# CubeControl.net
KiCad netlist of a schematic drawn in Altium Designer
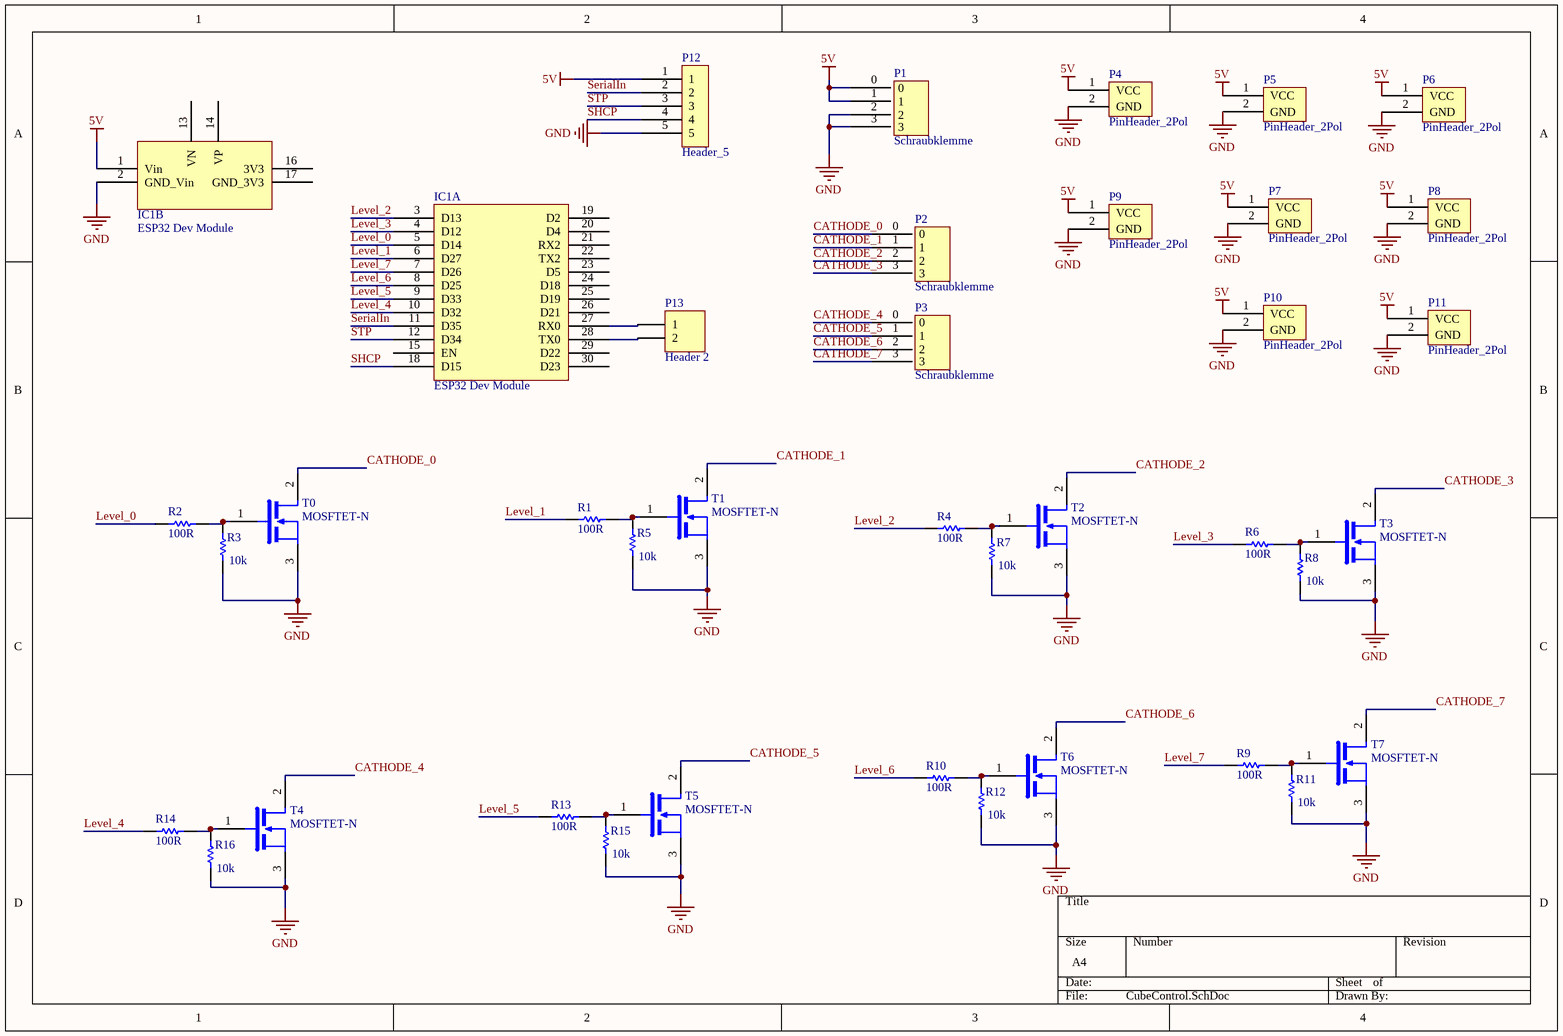
[diagram p0: CubeControl.SchDoc]

(export (version "E")
  (design (tool "Eeschema 10.0.6"))
  (components
    (comp (ref "IC1")
      (value "ESP32 Dev Module")
      (footprint "ESP32 Dev Module")
      (libsource (lib "RGB-Cube") (part "ESP32 Dev Module"))
    )
    (comp (ref "P1")
      (value "Schraubklemme")
      (footprint "Schraubklemme 4Pol")
      (description "Reichelt: RND 205-00003")
      (libsource (lib "RGB-Cube") (part "Schraubklemme"))
    )
    (comp (ref "P2")
      (value "Schraubklemme")
      (footprint "Schraubklemme 4Pol")
      (description "Reichelt: RND 205-00003")
      (libsource (lib "RGB-Cube") (part "Schraubklemme"))
    )
    (comp (ref "P3")
      (value "Schraubklemme")
      (footprint "Schraubklemme 4Pol")
      (description "Reichelt: RND 205-00003")
      (libsource (lib "RGB-Cube") (part "Schraubklemme"))
    )
    (comp (ref "P4")
      (value "PinHeader_2Pol")
      (footprint "PinHeader_2Pol")
      (libsource (lib "RGB-Cube") (part "PinHeader_2Pol"))
    )
    (comp (ref "P5")
      (value "PinHeader_2Pol")
      (footprint "PinHeader_2Pol")
      (libsource (lib "RGB-Cube") (part "PinHeader_2Pol"))
    )
    (comp (ref "P6")
      (value "PinHeader_2Pol")
      (footprint "PinHeader_2Pol")
      (libsource (lib "RGB-Cube") (part "PinHeader_2Pol"))
    )
    (comp (ref "P7")
      (value "PinHeader_2Pol")
      (footprint "PinHeader_2Pol")
      (libsource (lib "RGB-Cube") (part "PinHeader_2Pol"))
    )
    (comp (ref "P8")
      (value "PinHeader_2Pol")
      (footprint "PinHeader_2Pol")
      (libsource (lib "RGB-Cube") (part "PinHeader_2Pol"))
    )
    (comp (ref "P9")
      (value "PinHeader_2Pol")
      (footprint "PinHeader_2Pol")
      (libsource (lib "RGB-Cube") (part "PinHeader_2Pol"))
    )
    (comp (ref "P10")
      (value "PinHeader_2Pol")
      (footprint "PinHeader_2Pol")
      (libsource (lib "RGB-Cube") (part "PinHeader_2Pol"))
    )
    (comp (ref "P11")
      (value "PinHeader_2Pol")
      (footprint "PinHeader_2Pol")
      (libsource (lib "RGB-Cube") (part "PinHeader_2Pol"))
    )
    (comp (ref "P12")
      (value "Header_5")
      (footprint "PinHeader")
      (libsource (lib "RGB-Cube") (part "Header_5"))
    )
    (comp (ref "P13")
      (value "Header 2")
      (footprint "HDR1X2")
      (description "Header, 2-Pin")
      (fields (field (name "PUBLISHER") "Altium Limited"))
      (libsource (lib "Miscellaneous Connectors") (part "Header 2"))
    )
    (comp (ref "R1")
      (value "100R")
      (footprint "RESC1206(3216)_M")
      (description "2R 0.25W 5% 1206 (3216 Metric)  SMD")
      (fields (field (name "TOLERANCE") "5 %") (field (name "POWER") "0.25 W"))
      (libsource (lib "Altium Content Vault") (part "CMP-1014-00009-1"))
    )
    (comp (ref "R2")
      (value "100R")
      (footprint "RESC1206(3216)_M")
      (description "2R 0.25W 5% 1206 (3216 Metric)  SMD")
      (fields (field (name "TOLERANCE") "5 %") (field (name "POWER") "0.25 W"))
      (libsource (lib "Altium Content Vault") (part "CMP-1014-00009-1"))
    )
    (comp (ref "R3")
      (value "10k")
      (footprint "RESC1206(3216)_M")
      (description "43k 0.25W 5% 1206 (3216 Metric)  SMD")
      (fields (field (name "TOLERANCE") "5 %") (field (name "POWER") "0.25 W"))
      (libsource (lib "Altium Content Vault") (part "CMP-1014-00009-1"))
    )
    (comp (ref "R4")
      (value "100R")
      (footprint "RESC1206(3216)_M")
      (description "2R 0.25W 5% 1206 (3216 Metric)  SMD")
      (fields (field (name "TOLERANCE") "5 %") (field (name "POWER") "0.25 W"))
      (libsource (lib "Altium Content Vault") (part "CMP-1014-00009-1"))
    )
    (comp (ref "R5")
      (value "10k")
      (footprint "RESC1206(3216)_M")
      (description "43k 0.25W 5% 1206 (3216 Metric)  SMD")
      (fields (field (name "TOLERANCE") "5 %") (field (name "POWER") "0.25 W"))
      (libsource (lib "Altium Content Vault") (part "CMP-1014-00009-1"))
    )
    (comp (ref "R6")
      (value "100R")
      (footprint "RESC1206(3216)_M")
      (description "2R 0.25W 5% 1206 (3216 Metric)  SMD")
      (fields (field (name "TOLERANCE") "5 %") (field (name "POWER") "0.25 W"))
      (libsource (lib "Altium Content Vault") (part "CMP-1014-00009-1"))
    )
    (comp (ref "R7")
      (value "10k")
      (footprint "RESC1206(3216)_M")
      (description "43k 0.25W 5% 1206 (3216 Metric)  SMD")
      (fields (field (name "TOLERANCE") "5 %") (field (name "POWER") "0.25 W"))
      (libsource (lib "Altium Content Vault") (part "CMP-1014-00009-1"))
    )
    (comp (ref "R8")
      (value "10k")
      (footprint "RESC1206(3216)_M")
      (description "43k 0.25W 5% 1206 (3216 Metric)  SMD")
      (fields (field (name "TOLERANCE") "5 %") (field (name "POWER") "0.25 W"))
      (libsource (lib "Altium Content Vault") (part "CMP-1014-00009-1"))
    )
    (comp (ref "R9")
      (value "100R")
      (footprint "RESC1206(3216)_M")
      (description "2R 0.25W 5% 1206 (3216 Metric)  SMD")
      (fields (field (name "TOLERANCE") "5 %") (field (name "POWER") "0.25 W"))
      (libsource (lib "Altium Content Vault") (part "CMP-1014-00009-1"))
    )
    (comp (ref "R10")
      (value "100R")
      (footprint "RESC1206(3216)_M")
      (description "2R 0.25W 5% 1206 (3216 Metric)  SMD")
      (fields (field (name "TOLERANCE") "5 %") (field (name "POWER") "0.25 W"))
      (libsource (lib "Altium Content Vault") (part "CMP-1014-00009-1"))
    )
    (comp (ref "R11")
      (value "10k")
      (footprint "RESC1206(3216)_M")
      (description "43k 0.25W 5% 1206 (3216 Metric)  SMD")
      (fields (field (name "TOLERANCE") "5 %") (field (name "POWER") "0.25 W"))
      (libsource (lib "Altium Content Vault") (part "CMP-1014-00009-1"))
    )
    (comp (ref "R12")
      (value "10k")
      (footprint "RESC1206(3216)_M")
      (description "43k 0.25W 5% 1206 (3216 Metric)  SMD")
      (fields (field (name "TOLERANCE") "5 %") (field (name "POWER") "0.25 W"))
      (libsource (lib "Altium Content Vault") (part "CMP-1014-00009-1"))
    )
    (comp (ref "R13")
      (value "100R")
      (footprint "RESC1206(3216)_M")
      (description "2R 0.25W 5% 1206 (3216 Metric)  SMD")
      (fields (field (name "TOLERANCE") "5 %") (field (name "POWER") "0.25 W"))
      (libsource (lib "Altium Content Vault") (part "CMP-1014-00009-1"))
    )
    (comp (ref "R14")
      (value "100R")
      (footprint "RESC1206(3216)_M")
      (description "2R 0.25W 5% 1206 (3216 Metric)  SMD")
      (fields (field (name "TOLERANCE") "5 %") (field (name "POWER") "0.25 W"))
      (libsource (lib "Altium Content Vault") (part "CMP-1014-00009-1"))
    )
    (comp (ref "R15")
      (value "10k")
      (footprint "RESC1206(3216)_M")
      (description "43k 0.25W 5% 1206 (3216 Metric)  SMD")
      (fields (field (name "TOLERANCE") "5 %") (field (name "POWER") "0.25 W"))
      (libsource (lib "Altium Content Vault") (part "CMP-1014-00009-1"))
    )
    (comp (ref "R16")
      (value "10k")
      (footprint "RESC1206(3216)_M")
      (description "43k 0.25W 5% 1206 (3216 Metric)  SMD")
      (fields (field (name "TOLERANCE") "5 %") (field (name "POWER") "0.25 W"))
      (libsource (lib "Altium Content Vault") (part "CMP-1014-00009-1"))
    )
    (comp (ref "T0")
      (value "MOSFTET-N")
      (footprint "TO220-3")
      (description "Reichelt: IRF 3708")
      (libsource (lib "RGB-Cube") (part "Mosfet-N"))
    )
    (comp (ref "T1")
      (value "MOSFTET-N")
      (footprint "TO220-3")
      (description "Reichelt: IRF 3708")
      (libsource (lib "RGB-Cube") (part "Mosfet-N"))
    )
    (comp (ref "T2")
      (value "MOSFTET-N")
      (footprint "TO220-3")
      (description "Reichelt: IRF 3708")
      (libsource (lib "RGB-Cube") (part "Mosfet-N"))
    )
    (comp (ref "T3")
      (value "MOSFTET-N")
      (footprint "TO220-3")
      (description "Reichelt: IRF 3708")
      (libsource (lib "RGB-Cube") (part "Mosfet-N"))
    )
    (comp (ref "T4")
      (value "MOSFTET-N")
      (footprint "TO220-3")
      (description "Reichelt: IRF 3708")
      (libsource (lib "RGB-Cube") (part "Mosfet-N"))
    )
    (comp (ref "T5")
      (value "MOSFTET-N")
      (footprint "TO220-3")
      (description "Reichelt: IRF 3708")
      (libsource (lib "RGB-Cube") (part "Mosfet-N"))
    )
    (comp (ref "T6")
      (value "MOSFTET-N")
      (footprint "TO220-3")
      (description "Reichelt: IRF 3708")
      (libsource (lib "RGB-Cube") (part "Mosfet-N"))
    )
    (comp (ref "T7")
      (value "MOSFTET-N")
      (footprint "TO220-3")
      (description "Reichelt: IRF 3708")
      (libsource (lib "RGB-Cube") (part "Mosfet-N"))
    )
  )
  (nets
    (net (code "1") (name "/CATHODE_0") (class "Default")
      (node (ref "P2") (pin "0") (pinfunction "0_0") (pintype "passive"))
      (node (ref "T0") (pin "2") (pintype "passive"))
    )
    (net (code "2") (name "/CATHODE_1") (class "Default")
      (node (ref "P2") (pin "1") (pinfunction "1_1") (pintype "passive"))
      (node (ref "T1") (pin "2") (pintype "passive"))
    )
    (net (code "3") (name "/CATHODE_2") (class "Default")
      (node (ref "P2") (pin "2") (pinfunction "2_2") (pintype "passive"))
      (node (ref "T2") (pin "2") (pintype "passive"))
    )
    (net (code "4") (name "/CATHODE_3") (class "Default")
      (node (ref "P2") (pin "3") (pinfunction "3_3") (pintype "passive"))
      (node (ref "T3") (pin "2") (pintype "passive"))
    )
    (net (code "5") (name "/CATHODE_4") (class "Default")
      (node (ref "P3") (pin "0") (pinfunction "0_0") (pintype "passive"))
      (node (ref "T4") (pin "2") (pintype "passive"))
    )
    (net (code "6") (name "/CATHODE_5") (class "Default")
      (node (ref "P3") (pin "1") (pinfunction "1_1") (pintype "passive"))
      (node (ref "T5") (pin "2") (pintype "passive"))
    )
    (net (code "7") (name "/CATHODE_6") (class "Default")
      (node (ref "P3") (pin "2") (pinfunction "2_2") (pintype "passive"))
      (node (ref "T6") (pin "2") (pintype "passive"))
    )
    (net (code "8") (name "/CATHODE_7") (class "Default")
      (node (ref "P3") (pin "3") (pinfunction "3_3") (pintype "passive"))
      (node (ref "T7") (pin "2") (pintype "passive"))
    )
    (net (code "9") (name "/Level_0") (class "Default")
      (node (ref "IC1") (pin "5") (pinfunction "D14_5") (pintype "passive"))
      (node (ref "R2") (pin "1") (pinfunction "1_1") (pintype "passive"))
    )
    (net (code "10") (name "/Level_1") (class "Default")
      (node (ref "IC1") (pin "6") (pinfunction "D27_6") (pintype "passive"))
      (node (ref "R1") (pin "1") (pinfunction "1_1") (pintype "passive"))
    )
    (net (code "11") (name "/Level_2") (class "Default")
      (node (ref "IC1") (pin "3") (pinfunction "D13_3") (pintype "passive"))
      (node (ref "R4") (pin "1") (pinfunction "1_1") (pintype "passive"))
    )
    (net (code "12") (name "/Level_3") (class "Default")
      (node (ref "IC1") (pin "4") (pinfunction "D12_4") (pintype "passive"))
      (node (ref "R6") (pin "1") (pinfunction "1_1") (pintype "passive"))
    )
    (net (code "13") (name "/Level_4") (class "Default")
      (node (ref "IC1") (pin "10") (pinfunction "D32_10") (pintype "passive"))
      (node (ref "R14") (pin "1") (pinfunction "1_1") (pintype "passive"))
    )
    (net (code "14") (name "/Level_5") (class "Default")
      (node (ref "IC1") (pin "9") (pinfunction "D33_9") (pintype "passive"))
      (node (ref "R13") (pin "1") (pinfunction "1_1") (pintype "passive"))
    )
    (net (code "15") (name "/Level_6") (class "Default")
      (node (ref "IC1") (pin "8") (pinfunction "D25_8") (pintype "passive"))
      (node (ref "R10") (pin "1") (pinfunction "1_1") (pintype "passive"))
    )
    (net (code "16") (name "/Level_7") (class "Default")
      (node (ref "IC1") (pin "7") (pinfunction "D26_7") (pintype "passive"))
      (node (ref "R9") (pin "1") (pinfunction "1_1") (pintype "passive"))
    )
    (net (code "17") (name "/SHCP") (class "Default")
      (node (ref "IC1") (pin "18") (pinfunction "D15_18") (pintype "passive"))
      (node (ref "P12") (pin "4") (pinfunction "4_4") (pintype "passive"))
    )
    (net (code "18") (name "/STP") (class "Default")
      (node (ref "IC1") (pin "12") (pinfunction "D34_12") (pintype "passive"))
      (node (ref "P12") (pin "3") (pinfunction "3_3") (pintype "passive"))
    )
    (net (code "19") (name "/SerialIn") (class "Default")
      (node (ref "IC1") (pin "11") (pinfunction "D35_11") (pintype "passive"))
      (node (ref "P12") (pin "2") (pinfunction "2_2") (pintype "passive"))
    )
    (net (code "20") (name "5V") (class "Default")
      (node (ref "IC1") (pin "1") (pinfunction "Vin_1") (pintype "passive"))
      (node (ref "P1") (pin "0") (pinfunction "0_0") (pintype "passive"))
      (node (ref "P1") (pin "1") (pinfunction "1_1") (pintype "passive"))
      (node (ref "P10") (pin "1") (pinfunction "VCC_1") (pintype "passive"))
      (node (ref "P11") (pin "1") (pinfunction "VCC_1") (pintype "passive"))
      (node (ref "P12") (pin "1") (pinfunction "1_1") (pintype "passive"))
      (node (ref "P4") (pin "1") (pinfunction "VCC_1") (pintype "passive"))
      (node (ref "P5") (pin "1") (pinfunction "VCC_1") (pintype "passive"))
      (node (ref "P6") (pin "1") (pinfunction "VCC_1") (pintype "passive"))
      (node (ref "P7") (pin "1") (pinfunction "VCC_1") (pintype "passive"))
      (node (ref "P8") (pin "1") (pinfunction "VCC_1") (pintype "passive"))
      (node (ref "P9") (pin "1") (pinfunction "VCC_1") (pintype "passive"))
    )
    (net (code "21") (name "GND") (class "Default")
      (node (ref "IC1") (pin "2") (pinfunction "GND_Vin_2") (pintype "passive"))
      (node (ref "P1") (pin "2") (pinfunction "2_2") (pintype "passive"))
      (node (ref "P1") (pin "3") (pinfunction "3_3") (pintype "passive"))
      (node (ref "P10") (pin "2") (pinfunction "GND_2") (pintype "passive"))
      (node (ref "P11") (pin "2") (pinfunction "GND_2") (pintype "passive"))
      (node (ref "P12") (pin "5") (pinfunction "5_5") (pintype "passive"))
      (node (ref "P4") (pin "2") (pinfunction "GND_2") (pintype "passive"))
      (node (ref "P5") (pin "2") (pinfunction "GND_2") (pintype "passive"))
      (node (ref "P6") (pin "2") (pinfunction "GND_2") (pintype "passive"))
      (node (ref "P7") (pin "2") (pinfunction "GND_2") (pintype "passive"))
      (node (ref "P8") (pin "2") (pinfunction "GND_2") (pintype "passive"))
      (node (ref "P9") (pin "2") (pinfunction "GND_2") (pintype "passive"))
      (node (ref "R11") (pin "1") (pinfunction "1_1") (pintype "passive"))
      (node (ref "R12") (pin "1") (pinfunction "1_1") (pintype "passive"))
      (node (ref "R15") (pin "1") (pinfunction "1_1") (pintype "passive"))
      (node (ref "R16") (pin "1") (pinfunction "1_1") (pintype "passive"))
      (node (ref "R3") (pin "1") (pinfunction "1_1") (pintype "passive"))
      (node (ref "R5") (pin "1") (pinfunction "1_1") (pintype "passive"))
      (node (ref "R7") (pin "1") (pinfunction "1_1") (pintype "passive"))
      (node (ref "R8") (pin "1") (pinfunction "1_1") (pintype "passive"))
      (node (ref "T0") (pin "3") (pintype "passive"))
      (node (ref "T1") (pin "3") (pintype "passive"))
      (node (ref "T2") (pin "3") (pintype "passive"))
      (node (ref "T3") (pin "3") (pintype "passive"))
      (node (ref "T4") (pin "3") (pintype "passive"))
      (node (ref "T5") (pin "3") (pintype "passive"))
      (node (ref "T6") (pin "3") (pintype "passive"))
      (node (ref "T7") (pin "3") (pintype "passive"))
    )
    (net (code "22") (name "Net-(IC1A-RX0)") (class "Default")
      (node (ref "IC1") (pin "27") (pinfunction "RX0_27") (pintype "passive"))
      (node (ref "P13") (pin "1") (pinfunction "1_1") (pintype "passive"))
    )
    (net (code "23") (name "Net-(IC1A-TX0)") (class "Default")
      (node (ref "IC1") (pin "28") (pinfunction "TX0_28") (pintype "passive"))
      (node (ref "P13") (pin "2") (pinfunction "2_2") (pintype "passive"))
    )
    (net (code "24") (name "Net-(R1-Pad2)") (class "Default")
      (node (ref "R1") (pin "2") (pinfunction "2_2") (pintype "passive"))
      (node (ref "R5") (pin "2") (pinfunction "2_2") (pintype "passive"))
      (node (ref "T1") (pin "1") (pintype "passive"))
    )
    (net (code "25") (name "Net-(R2-Pad2)") (class "Default")
      (node (ref "R2") (pin "2") (pinfunction "2_2") (pintype "passive"))
      (node (ref "R3") (pin "2") (pinfunction "2_2") (pintype "passive"))
      (node (ref "T0") (pin "1") (pintype "passive"))
    )
    (net (code "26") (name "Net-(R4-Pad2)") (class "Default")
      (node (ref "R4") (pin "2") (pinfunction "2_2") (pintype "passive"))
      (node (ref "R7") (pin "2") (pinfunction "2_2") (pintype "passive"))
      (node (ref "T2") (pin "1") (pintype "passive"))
    )
    (net (code "27") (name "Net-(R6-Pad2)") (class "Default")
      (node (ref "R6") (pin "2") (pinfunction "2_2") (pintype "passive"))
      (node (ref "R8") (pin "2") (pinfunction "2_2") (pintype "passive"))
      (node (ref "T3") (pin "1") (pintype "passive"))
    )
    (net (code "28") (name "Net-(R10-Pad2)") (class "Default")
      (node (ref "R10") (pin "2") (pinfunction "2_2") (pintype "passive"))
      (node (ref "R12") (pin "2") (pinfunction "2_2") (pintype "passive"))
      (node (ref "T6") (pin "1") (pintype "passive"))
    )
    (net (code "29") (name "Net-(R11-Pad2)") (class "Default")
      (node (ref "R11") (pin "2") (pinfunction "2_2") (pintype "passive"))
      (node (ref "R9") (pin "2") (pinfunction "2_2") (pintype "passive"))
      (node (ref "T7") (pin "1") (pintype "passive"))
    )
    (net (code "30") (name "Net-(R13-Pad2)") (class "Default")
      (node (ref "R13") (pin "2") (pinfunction "2_2") (pintype "passive"))
      (node (ref "R15") (pin "2") (pinfunction "2_2") (pintype "passive"))
      (node (ref "T5") (pin "1") (pintype "passive"))
    )
    (net (code "31") (name "Net-(R14-Pad2)") (class "Default")
      (node (ref "R14") (pin "2") (pinfunction "2_2") (pintype "passive"))
      (node (ref "R16") (pin "2") (pinfunction "2_2") (pintype "passive"))
      (node (ref "T4") (pin "1") (pintype "passive"))
    )
    (net (code "32") (name "unconnected-(IC1A-D2-Pad19)") (class "Default")
      (node (ref "IC1") (pin "19") (pinfunction "D2_19") (pintype "passive"))
    )
    (net (code "33") (name "unconnected-(IC1A-D4-Pad20)") (class "Default")
      (node (ref "IC1") (pin "20") (pinfunction "D4_20") (pintype "passive"))
    )
    (net (code "34") (name "unconnected-(IC1A-D5-Pad23)") (class "Default")
      (node (ref "IC1") (pin "23") (pinfunction "D5_23") (pintype "passive"))
    )
    (net (code "35") (name "unconnected-(IC1A-D18-Pad24)") (class "Default")
      (node (ref "IC1") (pin "24") (pinfunction "D18_24") (pintype "passive"))
    )
    (net (code "36") (name "unconnected-(IC1A-D19-Pad25)") (class "Default")
      (node (ref "IC1") (pin "25") (pinfunction "D19_25") (pintype "passive"))
    )
    (net (code "37") (name "unconnected-(IC1A-D21-Pad26)") (class "Default")
      (node (ref "IC1") (pin "26") (pinfunction "D21_26") (pintype "passive"))
    )
    (net (code "38") (name "unconnected-(IC1A-D22-Pad29)") (class "Default")
      (node (ref "IC1") (pin "29") (pinfunction "D22_29") (pintype "passive"))
    )
    (net (code "39") (name "unconnected-(IC1A-D23-Pad30)") (class "Default")
      (node (ref "IC1") (pin "30") (pinfunction "D23_30") (pintype "passive"))
    )
    (net (code "40") (name "unconnected-(IC1A-EN-Pad15)") (class "Default")
      (node (ref "IC1") (pin "15") (pinfunction "EN_15") (pintype "passive"))
    )
    (net (code "41") (name "unconnected-(IC1A-RX2-Pad21)") (class "Default")
      (node (ref "IC1") (pin "21") (pinfunction "RX2_21") (pintype "passive"))
    )
    (net (code "42") (name "unconnected-(IC1A-TX2-Pad22)") (class "Default")
      (node (ref "IC1") (pin "22") (pinfunction "TX2_22") (pintype "passive"))
    )
    (net (code "43") (name "unconnected-(IC1B-3V3-Pad16)") (class "Default")
      (node (ref "IC1") (pin "16") (pinfunction "3V3_16") (pintype "passive"))
    )
    (net (code "44") (name "unconnected-(IC1B-GND_3V3-Pad17)") (class "Default")
      (node (ref "IC1") (pin "17") (pinfunction "GND_3V3_17") (pintype "passive"))
    )
    (net (code "45") (name "unconnected-(IC1B-VN-Pad13)") (class "Default")
      (node (ref "IC1") (pin "13") (pinfunction "VN_13") (pintype "passive"))
    )
    (net (code "46") (name "unconnected-(IC1B-VP-Pad14)") (class "Default")
      (node (ref "IC1") (pin "14") (pinfunction "VP_14") (pintype "passive"))
    )
  )
)
